# MCU.net
KiCad netlist of a schematic drawn in Altium Designer
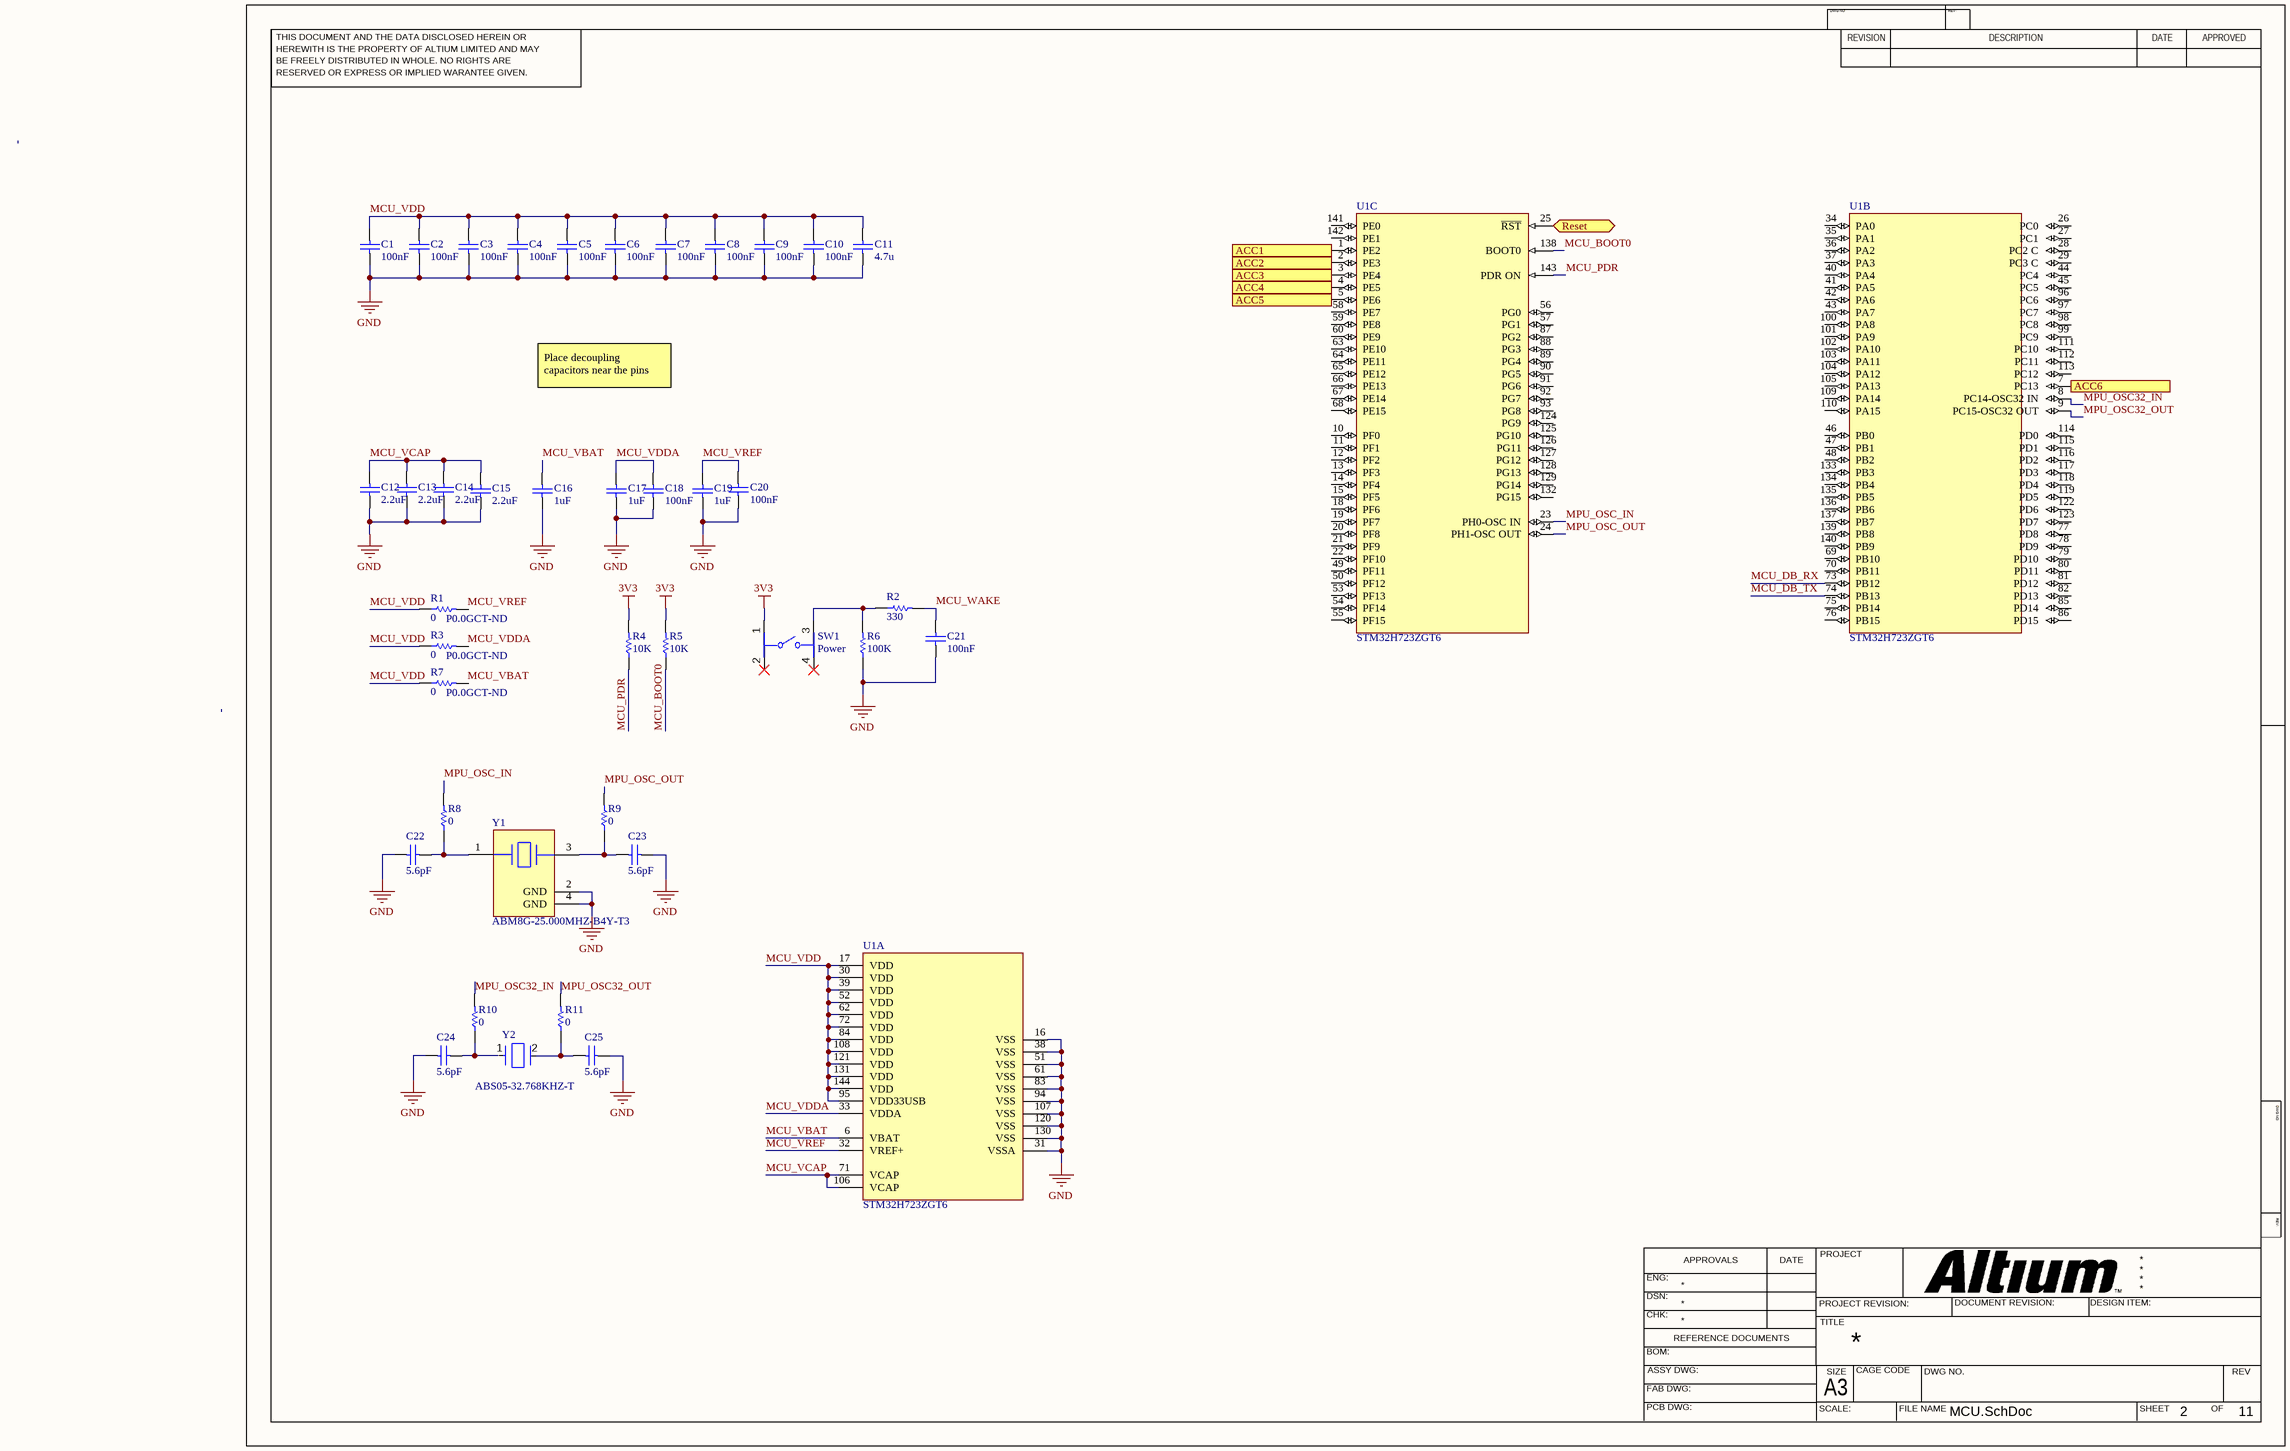
[diagram p0: MCU.SchDoc]

(export (version "E")
  (design (tool "Eeschema 10.0.6"))
  (components
    (comp (ref "C1")
      (value "100nF")
      (description "Capacitor")
      (libsource (lib "Simulation Generic Components") (part "Capacitor"))
    )
    (comp (ref "C2")
      (value "100nF")
      (description "Capacitor")
      (libsource (lib "Simulation Generic Components") (part "Capacitor"))
    )
    (comp (ref "C3")
      (value "100nF")
      (description "Capacitor")
      (libsource (lib "Simulation Generic Components") (part "Capacitor"))
    )
    (comp (ref "C4")
      (value "100nF")
      (description "Capacitor")
      (libsource (lib "Simulation Generic Components") (part "Capacitor"))
    )
    (comp (ref "C5")
      (value "100nF")
      (description "Capacitor")
      (libsource (lib "Simulation Generic Components") (part "Capacitor"))
    )
    (comp (ref "C6")
      (value "100nF")
      (description "Capacitor")
      (libsource (lib "Simulation Generic Components") (part "Capacitor"))
    )
    (comp (ref "C7")
      (value "100nF")
      (description "Capacitor")
      (libsource (lib "Simulation Generic Components") (part "Capacitor"))
    )
    (comp (ref "C8")
      (value "100nF")
      (description "Capacitor")
      (libsource (lib "Simulation Generic Components") (part "Capacitor"))
    )
    (comp (ref "C9")
      (value "100nF")
      (description "Capacitor")
      (libsource (lib "Simulation Generic Components") (part "Capacitor"))
    )
    (comp (ref "C10")
      (value "100nF")
      (description "Capacitor")
      (libsource (lib "Simulation Generic Components") (part "Capacitor"))
    )
    (comp (ref "C11")
      (value "4.7u")
      (description "Capacitor")
      (libsource (lib "Simulation Generic Components") (part "Capacitor"))
    )
    (comp (ref "C12")
      (value "2.2uF")
      (description "Capacitor")
      (libsource (lib "Simulation Generic Components") (part "Capacitor"))
    )
    (comp (ref "C13")
      (value "2.2uF")
      (description "Capacitor")
      (libsource (lib "Simulation Generic Components") (part "Capacitor"))
    )
    (comp (ref "C14")
      (value "2.2uF")
      (description "Capacitor")
      (libsource (lib "Simulation Generic Components") (part "Capacitor"))
    )
    (comp (ref "C15")
      (value "2.2uF")
      (description "Capacitor")
      (libsource (lib "Simulation Generic Components") (part "Capacitor"))
    )
    (comp (ref "C16")
      (value "1uF")
      (description "Capacitor")
      (libsource (lib "Simulation Generic Components") (part "Capacitor"))
    )
    (comp (ref "C17")
      (value "1uF")
      (description "Capacitor")
      (libsource (lib "Simulation Generic Components") (part "Capacitor"))
    )
    (comp (ref "C18")
      (value "100nF")
      (description "Capacitor")
      (libsource (lib "Simulation Generic Components") (part "Capacitor"))
    )
    (comp (ref "C19")
      (value "1uF")
      (description "Capacitor")
      (libsource (lib "Simulation Generic Components") (part "Capacitor"))
    )
    (comp (ref "C20")
      (value "100nF")
      (description "Capacitor")
      (libsource (lib "Simulation Generic Components") (part "Capacitor"))
    )
    (comp (ref "C21")
      (value "100nF")
      (description "Capacitor")
      (libsource (lib "Simulation Generic Components") (part "Capacitor"))
    )
    (comp (ref "C22")
      (value "5.6pF")
      (description "Capacitor")
      (libsource (lib "Simulation Generic Components") (part "Capacitor"))
    )
    (comp (ref "C23")
      (value "5.6pF")
      (description "Capacitor")
      (libsource (lib "Simulation Generic Components") (part "Capacitor"))
    )
    (comp (ref "C24")
      (value "5.6pF")
      (description "Capacitor")
      (libsource (lib "Simulation Generic Components") (part "Capacitor"))
    )
    (comp (ref "C25")
      (value "5.6pF")
      (description "Capacitor")
      (libsource (lib "Simulation Generic Components") (part "Capacitor"))
    )
    (comp (ref "R1")
      (value "0")
      (description "Resistor")
      (fields (field (name "SUPPLIER PART NUMBER 1") "P0.0GCT-ND"))
      (libsource (lib "Simulation Generic Components") (part "Resistor"))
    )
    (comp (ref "R2")
      (value "330")
      (description "Resistor")
      (libsource (lib "Simulation Generic Components") (part "Resistor"))
    )
    (comp (ref "R3")
      (value "0")
      (description "Resistor")
      (fields (field (name "SUPPLIER PART NUMBER 1") "P0.0GCT-ND"))
      (libsource (lib "Simulation Generic Components") (part "Resistor"))
    )
    (comp (ref "R4")
      (value "10K")
      (description "Resistor")
      (libsource (lib "Simulation Generic Components") (part "Resistor"))
    )
    (comp (ref "R5")
      (value "10K")
      (description "Resistor")
      (libsource (lib "Simulation Generic Components") (part "Resistor"))
    )
    (comp (ref "R6")
      (value "100K")
      (description "Resistor")
      (libsource (lib "Simulation Generic Components") (part "Resistor"))
    )
    (comp (ref "R7")
      (value "0")
      (description "Resistor")
      (fields (field (name "SUPPLIER PART NUMBER 1") "P0.0GCT-ND"))
      (libsource (lib "Simulation Generic Components") (part "Resistor"))
    )
    (comp (ref "R8")
      (value "0")
      (description "Resistor")
      (libsource (lib "Simulation Generic Components") (part "Resistor"))
    )
    (comp (ref "R9")
      (value "0")
      (description "Resistor")
      (libsource (lib "Simulation Generic Components") (part "Resistor"))
    )
    (comp (ref "R10")
      (value "0")
      (description "Resistor")
      (libsource (lib "Simulation Generic Components") (part "Resistor"))
    )
    (comp (ref "R11")
      (value "0")
      (description "Resistor")
      (libsource (lib "Simulation Generic Components") (part "Resistor"))
    )
    (comp (ref "SW1")
      (value "Power")
      (footprint "FP-PTS526SK15SMTR2LFS-MFG")
      (description "TACT 5.2 X 5.2, 1.5 MM H, 260GF,")
      (fields
        (field (name "MANUFACTURER") "C&K")
        (field (name "MANUFACTURER PART NUMBER") "PTS526SK15SMTR2LFS")
      )
      (libsource (lib "Altium Content Vault") (part "b8895f3f4cefb76e1819d2863dba89b"))
    )
    (comp (ref "U1")
      (value "STM32H723ZGT6")
      (footprint "FP-LQFP144-1A-IPC_A")
      (description "IC MCU 32BIT 1MB FLASH 144LQFP")
      (libsource (lib "Altium Content Vault") (part "099c9e622ff36f7eb897f9cba6d1f51"))
    )
    (comp (ref "Y1")
      (value "ABM8G-25.000MHZ-B4Y-T3")
      (footprint "FP-ABM8G-MFG")
      (description "Crystal 25MHz ±30ppm (Tol) ±30ppm (Stability) 10pF FUND 60Ω 4-Pin SMD T/R")
      (fields (field (name "TOLERANCE") "30ppm"))
      (libsource (lib "Altium Content Vault") (part "48e526d86b7f2615d98721063c72f49"))
    )
    (comp (ref "Y2")
      (value "ABS05-32.768KHZ-T")
      (footprint "FP-ABS05-MFG")
      (description "Crystal 32.768kHz ±20ppm (Tol) 12.5pF FUND 90kΩ 2-Pin SMD T/R")
      (fields (field (name "TOLERANCE") "20ppm"))
      (libsource (lib "Altium Content Vault") (part "c23a69dc6c9e2f18f2079038eb95dd1"))
    )
  )
  (nets
    (net (code "1") (name "/ACC1") (class "Default")
      (node (ref "U1") (pin "1") (pinfunction "PE2_1") (pintype "bidirectional"))
    )
    (net (code "2") (name "/ACC2") (class "Default")
      (node (ref "U1") (pin "2") (pinfunction "PE3_2") (pintype "bidirectional"))
    )
    (net (code "3") (name "/ACC3") (class "Default")
      (node (ref "U1") (pin "3") (pinfunction "PE4_3") (pintype "bidirectional"))
    )
    (net (code "4") (name "/ACC4") (class "Default")
      (node (ref "U1") (pin "4") (pinfunction "PE5_4") (pintype "bidirectional"))
    )
    (net (code "5") (name "/ACC5") (class "Default")
      (node (ref "U1") (pin "5") (pinfunction "PE6_5") (pintype "bidirectional"))
    )
    (net (code "6") (name "/ACC6") (class "Default")
      (node (ref "U1") (pin "7") (pinfunction "PC13_7") (pintype "bidirectional"))
    )
    (net (code "7") (name "/MCU_BOOT0") (class "Default")
      (node (ref "R5") (pin "1") (pinfunction "1_1") (pintype "passive"))
      (node (ref "U1") (pin "138") (pinfunction "BOOT0_138") (pintype "input"))
    )
    (net (code "8") (name "/MCU_DB_RX") (class "Default")
      (node (ref "U1") (pin "73") (pinfunction "PB12_73") (pintype "bidirectional"))
    )
    (net (code "9") (name "/MCU_DB_TX") (class "Default")
      (node (ref "U1") (pin "74") (pinfunction "PB13_74") (pintype "bidirectional"))
    )
    (net (code "10") (name "/MCU_PDR") (class "Default")
      (node (ref "R4") (pin "1") (pinfunction "1_1") (pintype "passive"))
      (node (ref "U1") (pin "143") (pinfunction "PDR_ON_143") (pintype "input"))
    )
    (net (code "11") (name "/MCU_VBAT") (class "Default")
      (node (ref "C16") (pin "2") (pinfunction "2_2") (pintype "passive"))
      (node (ref "U1") (pin "6") (pinfunction "VBAT_6") (pintype "power_in"))
    )
    (net (code "12") (name "/MCU_VCAP") (class "Default")
      (node (ref "C12") (pin "2") (pinfunction "2_2") (pintype "passive"))
      (node (ref "C13") (pin "2") (pinfunction "2_2") (pintype "passive"))
      (node (ref "C14") (pin "2") (pinfunction "2_2") (pintype "passive"))
      (node (ref "C15") (pin "2") (pinfunction "2_2") (pintype "passive"))
      (node (ref "U1") (pin "106") (pinfunction "VCAP_106") (pintype "power_in"))
      (node (ref "U1") (pin "71") (pinfunction "VCAP_71") (pintype "power_in"))
    )
    (net (code "13") (name "/MCU_VDD") (class "Default")
      (node (ref "C1") (pin "2") (pinfunction "2_2") (pintype "passive"))
      (node (ref "C10") (pin "2") (pinfunction "2_2") (pintype "passive"))
      (node (ref "C11") (pin "2") (pinfunction "2_2") (pintype "passive"))
      (node (ref "C2") (pin "2") (pinfunction "2_2") (pintype "passive"))
      (node (ref "C3") (pin "2") (pinfunction "2_2") (pintype "passive"))
      (node (ref "C4") (pin "2") (pinfunction "2_2") (pintype "passive"))
      (node (ref "C5") (pin "2") (pinfunction "2_2") (pintype "passive"))
      (node (ref "C6") (pin "2") (pinfunction "2_2") (pintype "passive"))
      (node (ref "C7") (pin "2") (pinfunction "2_2") (pintype "passive"))
      (node (ref "C8") (pin "2") (pinfunction "2_2") (pintype "passive"))
      (node (ref "C9") (pin "2") (pinfunction "2_2") (pintype "passive"))
      (node (ref "R1") (pin "1") (pinfunction "1_1") (pintype "passive"))
      (node (ref "R3") (pin "1") (pinfunction "1_1") (pintype "passive"))
      (node (ref "R7") (pin "1") (pinfunction "1_1") (pintype "passive"))
      (node (ref "U1") (pin "108") (pinfunction "VDD_108") (pintype "power_in"))
      (node (ref "U1") (pin "121") (pinfunction "VDD_121") (pintype "power_in"))
      (node (ref "U1") (pin "131") (pinfunction "VDD_131") (pintype "power_in"))
      (node (ref "U1") (pin "144") (pinfunction "VDD_144") (pintype "power_in"))
      (node (ref "U1") (pin "17") (pinfunction "VDD_17") (pintype "power_in"))
      (node (ref "U1") (pin "30") (pinfunction "VDD_30") (pintype "power_in"))
      (node (ref "U1") (pin "39") (pinfunction "VDD_39") (pintype "power_in"))
      (node (ref "U1") (pin "52") (pinfunction "VDD_52") (pintype "power_in"))
      (node (ref "U1") (pin "62") (pinfunction "VDD_62") (pintype "power_in"))
      (node (ref "U1") (pin "72") (pinfunction "VDD_72") (pintype "power_in"))
      (node (ref "U1") (pin "84") (pinfunction "VDD_84") (pintype "power_in"))
      (node (ref "U1") (pin "95") (pinfunction "VDD33USB_95") (pintype "power_in"))
    )
    (net (code "14") (name "/MCU_VDDA") (class "Default")
      (node (ref "C17") (pin "2") (pinfunction "2_2") (pintype "passive"))
      (node (ref "C18") (pin "2") (pinfunction "2_2") (pintype "passive"))
      (node (ref "U1") (pin "33") (pinfunction "VDDA_33") (pintype "power_in"))
    )
    (net (code "15") (name "/MCU_VREF") (class "Default")
      (node (ref "C19") (pin "2") (pinfunction "2_2") (pintype "passive"))
      (node (ref "C20") (pin "2") (pinfunction "2_2") (pintype "passive"))
      (node (ref "U1") (pin "32") (pinfunction "VREF+_32") (pintype "power_in"))
    )
    (net (code "16") (name "/MCU_WAKE") (class "Default")
      (node (ref "C21") (pin "2") (pinfunction "2_2") (pintype "passive"))
      (node (ref "R2") (pin "2") (pinfunction "2_2") (pintype "passive"))
    )
    (net (code "17") (name "/MPU_OSC32_IN") (class "Default")
      (node (ref "R10") (pin "2") (pinfunction "2_2") (pintype "passive"))
      (node (ref "U1") (pin "8") (pinfunction "PC14-OSC32_IN_8") (pintype "bidirectional"))
    )
    (net (code "18") (name "/MPU_OSC32_OUT") (class "Default")
      (node (ref "R11") (pin "2") (pinfunction "2_2") (pintype "passive"))
      (node (ref "U1") (pin "9") (pinfunction "PC15-OSC32_OUT_9") (pintype "bidirectional"))
    )
    (net (code "19") (name "/MPU_OSC_IN") (class "Default")
      (node (ref "R8") (pin "2") (pinfunction "2_2") (pintype "passive"))
      (node (ref "U1") (pin "23") (pinfunction "PH0-OSC_IN_23") (pintype "bidirectional"))
    )
    (net (code "20") (name "/MPU_OSC_OUT") (class "Default")
      (node (ref "R9") (pin "2") (pinfunction "2_2") (pintype "passive"))
      (node (ref "U1") (pin "24") (pinfunction "PH1-OSC_OUT_24") (pintype "bidirectional"))
    )
    (net (code "21") (name "/Reset") (class "Default")
      (node (ref "U1") (pin "25") (pinfunction "~{RST}_25") (pintype "input"))
    )
    (net (code "22") (name "3V3") (class "Default")
      (node (ref "R4") (pin "2") (pinfunction "2_2") (pintype "passive"))
      (node (ref "R5") (pin "2") (pinfunction "2_2") (pintype "passive"))
      (node (ref "SW1") (pin "1") (pinfunction "1_1") (pintype "passive"))
    )
    (net (code "23") (name "GND") (class "Default")
      (node (ref "C1") (pin "1") (pinfunction "1_1") (pintype "passive"))
      (node (ref "C10") (pin "1") (pinfunction "1_1") (pintype "passive"))
      (node (ref "C11") (pin "1") (pinfunction "1_1") (pintype "passive"))
      (node (ref "C12") (pin "1") (pinfunction "1_1") (pintype "passive"))
      (node (ref "C13") (pin "1") (pinfunction "1_1") (pintype "passive"))
      (node (ref "C14") (pin "1") (pinfunction "1_1") (pintype "passive"))
      (node (ref "C15") (pin "1") (pinfunction "1_1") (pintype "passive"))
      (node (ref "C16") (pin "1") (pinfunction "1_1") (pintype "passive"))
      (node (ref "C17") (pin "1") (pinfunction "1_1") (pintype "passive"))
      (node (ref "C18") (pin "1") (pinfunction "1_1") (pintype "passive"))
      (node (ref "C19") (pin "1") (pinfunction "1_1") (pintype "passive"))
      (node (ref "C2") (pin "1") (pinfunction "1_1") (pintype "passive"))
      (node (ref "C20") (pin "1") (pinfunction "1_1") (pintype "passive"))
      (node (ref "C21") (pin "1") (pinfunction "1_1") (pintype "passive"))
      (node (ref "C22") (pin "2") (pinfunction "2_2") (pintype "passive"))
      (node (ref "C23") (pin "1") (pinfunction "1_1") (pintype "passive"))
      (node (ref "C24") (pin "2") (pinfunction "2_2") (pintype "passive"))
      (node (ref "C25") (pin "1") (pinfunction "1_1") (pintype "passive"))
      (node (ref "C3") (pin "1") (pinfunction "1_1") (pintype "passive"))
      (node (ref "C4") (pin "1") (pinfunction "1_1") (pintype "passive"))
      (node (ref "C5") (pin "1") (pinfunction "1_1") (pintype "passive"))
      (node (ref "C6") (pin "1") (pinfunction "1_1") (pintype "passive"))
      (node (ref "C7") (pin "1") (pinfunction "1_1") (pintype "passive"))
      (node (ref "C8") (pin "1") (pinfunction "1_1") (pintype "passive"))
      (node (ref "C9") (pin "1") (pinfunction "1_1") (pintype "passive"))
      (node (ref "R6") (pin "1") (pinfunction "1_1") (pintype "passive"))
      (node (ref "U1") (pin "107") (pinfunction "VSS_107") (pintype "power_in"))
      (node (ref "U1") (pin "120") (pinfunction "VSS_120") (pintype "power_in"))
      (node (ref "U1") (pin "130") (pinfunction "VSS_130") (pintype "power_in"))
      (node (ref "U1") (pin "16") (pinfunction "VSS_16") (pintype "power_in"))
      (node (ref "U1") (pin "31") (pinfunction "VSSA_31") (pintype "power_in"))
      (node (ref "U1") (pin "38") (pinfunction "VSS_38") (pintype "power_in"))
      (node (ref "U1") (pin "51") (pinfunction "VSS_51") (pintype "power_in"))
      (node (ref "U1") (pin "61") (pinfunction "VSS_61") (pintype "power_in"))
      (node (ref "U1") (pin "83") (pinfunction "VSS_83") (pintype "power_in"))
      (node (ref "U1") (pin "94") (pinfunction "VSS_94") (pintype "power_in"))
      (node (ref "Y1") (pin "2") (pinfunction "GND_2") (pintype "power_in"))
      (node (ref "Y1") (pin "4") (pinfunction "GND_4") (pintype "power_in"))
    )
    (net (code "24") (name "Net-(C22-Pad1)") (class "Default")
      (node (ref "C22") (pin "1") (pinfunction "1_1") (pintype "passive"))
      (node (ref "R8") (pin "1") (pinfunction "1_1") (pintype "passive"))
      (node (ref "Y1") (pin "1") (pinfunction "1_1") (pintype "passive"))
    )
    (net (code "25") (name "Net-(C23-Pad2)") (class "Default")
      (node (ref "C23") (pin "2") (pinfunction "2_2") (pintype "passive"))
      (node (ref "R9") (pin "1") (pinfunction "1_1") (pintype "passive"))
      (node (ref "Y1") (pin "3") (pinfunction "3_3") (pintype "passive"))
    )
    (net (code "26") (name "Net-(C24-Pad1)") (class "Default")
      (node (ref "C24") (pin "1") (pinfunction "1_1") (pintype "passive"))
      (node (ref "R10") (pin "1") (pinfunction "1_1") (pintype "passive"))
    )
    (net (code "27") (name "Net-(C25-Pad2)") (class "Default")
      (node (ref "C25") (pin "2") (pinfunction "2_2") (pintype "passive"))
      (node (ref "R11") (pin "1") (pinfunction "1_1") (pintype "passive"))
      (node (ref "Y2") (pin "2") (pinfunction "2_2") (pintype "passive"))
    )
    (net (code "28") (name "Net-(R2-Pad1)") (class "Default")
      (node (ref "R2") (pin "1") (pinfunction "1_1") (pintype "passive"))
      (node (ref "R6") (pin "2") (pinfunction "2_2") (pintype "passive"))
      (node (ref "SW1") (pin "3") (pinfunction "3_3") (pintype "passive"))
    )
    (net (code "29") (name "unconnected-(R1-Pad2)") (class "Default")
      (node (ref "R1") (pin "2") (pinfunction "2_2") (pintype "passive"))
    )
    (net (code "30") (name "unconnected-(R3-Pad2)") (class "Default")
      (node (ref "R3") (pin "2") (pinfunction "2_2") (pintype "passive"))
    )
    (net (code "31") (name "unconnected-(R7-Pad2)") (class "Default")
      (node (ref "R7") (pin "2") (pinfunction "2_2") (pintype "passive"))
    )
    (net (code "32") (name "unconnected-(SW1-Pad2)") (class "Default")
      (node (ref "SW1") (pin "2") (pinfunction "2_2") (pintype "passive+no_connect"))
    )
    (net (code "33") (name "unconnected-(SW1-Pad4)") (class "Default")
      (node (ref "SW1") (pin "4") (pinfunction "4_4") (pintype "passive+no_connect"))
    )
    (net (code "34") (name "unconnected-(U1B-PA0-Pad34)") (class "Default")
      (node (ref "U1") (pin "34") (pinfunction "PA0_34") (pintype "bidirectional"))
    )
    (net (code "35") (name "unconnected-(U1B-PA1-Pad35)") (class "Default")
      (node (ref "U1") (pin "35") (pinfunction "PA1_35") (pintype "bidirectional"))
    )
    (net (code "36") (name "unconnected-(U1B-PA2-Pad36)") (class "Default")
      (node (ref "U1") (pin "36") (pinfunction "PA2_36") (pintype "bidirectional"))
    )
    (net (code "37") (name "unconnected-(U1B-PA3-Pad37)") (class "Default")
      (node (ref "U1") (pin "37") (pinfunction "PA3_37") (pintype "bidirectional"))
    )
    (net (code "38") (name "unconnected-(U1B-PA4-Pad40)") (class "Default")
      (node (ref "U1") (pin "40") (pinfunction "PA4_40") (pintype "bidirectional"))
    )
    (net (code "39") (name "unconnected-(U1B-PA5-Pad41)") (class "Default")
      (node (ref "U1") (pin "41") (pinfunction "PA5_41") (pintype "bidirectional"))
    )
    (net (code "40") (name "unconnected-(U1B-PA6-Pad42)") (class "Default")
      (node (ref "U1") (pin "42") (pinfunction "PA6_42") (pintype "bidirectional"))
    )
    (net (code "41") (name "unconnected-(U1B-PA7-Pad43)") (class "Default")
      (node (ref "U1") (pin "43") (pinfunction "PA7_43") (pintype "bidirectional"))
    )
    (net (code "42") (name "unconnected-(U1B-PA8-Pad100)") (class "Default")
      (node (ref "U1") (pin "100") (pinfunction "PA8_100") (pintype "bidirectional"))
    )
    (net (code "43") (name "unconnected-(U1B-PA9-Pad101)") (class "Default")
      (node (ref "U1") (pin "101") (pinfunction "PA9_101") (pintype "bidirectional"))
    )
    (net (code "44") (name "unconnected-(U1B-PA10-Pad102)") (class "Default")
      (node (ref "U1") (pin "102") (pinfunction "PA10_102") (pintype "bidirectional"))
    )
    (net (code "45") (name "unconnected-(U1B-PA11-Pad103)") (class "Default")
      (node (ref "U1") (pin "103") (pinfunction "PA11_103") (pintype "bidirectional"))
    )
    (net (code "46") (name "unconnected-(U1B-PA12-Pad104)") (class "Default")
      (node (ref "U1") (pin "104") (pinfunction "PA12_104") (pintype "bidirectional"))
    )
    (net (code "47") (name "unconnected-(U1B-PA13-Pad105)") (class "Default")
      (node (ref "U1") (pin "105") (pinfunction "PA13_105") (pintype "bidirectional"))
    )
    (net (code "48") (name "unconnected-(U1B-PA14-Pad109)") (class "Default")
      (node (ref "U1") (pin "109") (pinfunction "PA14_109") (pintype "bidirectional"))
    )
    (net (code "49") (name "unconnected-(U1B-PA15-Pad110)") (class "Default")
      (node (ref "U1") (pin "110") (pinfunction "PA15_110") (pintype "bidirectional"))
    )
    (net (code "50") (name "unconnected-(U1B-PB0-Pad46)") (class "Default")
      (node (ref "U1") (pin "46") (pinfunction "PB0_46") (pintype "bidirectional"))
    )
    (net (code "51") (name "unconnected-(U1B-PB1-Pad47)") (class "Default")
      (node (ref "U1") (pin "47") (pinfunction "PB1_47") (pintype "bidirectional"))
    )
    (net (code "52") (name "unconnected-(U1B-PB2-Pad48)") (class "Default")
      (node (ref "U1") (pin "48") (pinfunction "PB2_48") (pintype "bidirectional"))
    )
    (net (code "53") (name "unconnected-(U1B-PB3-Pad133)") (class "Default")
      (node (ref "U1") (pin "133") (pinfunction "PB3_133") (pintype "bidirectional"))
    )
    (net (code "54") (name "unconnected-(U1B-PB4-Pad134)") (class "Default")
      (node (ref "U1") (pin "134") (pinfunction "PB4_134") (pintype "bidirectional"))
    )
    (net (code "55") (name "unconnected-(U1B-PB5-Pad135)") (class "Default")
      (node (ref "U1") (pin "135") (pinfunction "PB5_135") (pintype "bidirectional"))
    )
    (net (code "56") (name "unconnected-(U1B-PB6-Pad136)") (class "Default")
      (node (ref "U1") (pin "136") (pinfunction "PB6_136") (pintype "bidirectional"))
    )
    (net (code "57") (name "unconnected-(U1B-PB7-Pad137)") (class "Default")
      (node (ref "U1") (pin "137") (pinfunction "PB7_137") (pintype "bidirectional"))
    )
    (net (code "58") (name "unconnected-(U1B-PB8-Pad139)") (class "Default")
      (node (ref "U1") (pin "139") (pinfunction "PB8_139") (pintype "bidirectional"))
    )
    (net (code "59") (name "unconnected-(U1B-PB9-Pad140)") (class "Default")
      (node (ref "U1") (pin "140") (pinfunction "PB9_140") (pintype "bidirectional"))
    )
    (net (code "60") (name "unconnected-(U1B-PB10-Pad69)") (class "Default")
      (node (ref "U1") (pin "69") (pinfunction "PB10_69") (pintype "bidirectional"))
    )
    (net (code "61") (name "unconnected-(U1B-PB11-Pad70)") (class "Default")
      (node (ref "U1") (pin "70") (pinfunction "PB11_70") (pintype "bidirectional"))
    )
    (net (code "62") (name "unconnected-(U1B-PB14-Pad75)") (class "Default")
      (node (ref "U1") (pin "75") (pinfunction "PB14_75") (pintype "bidirectional"))
    )
    (net (code "63") (name "unconnected-(U1B-PB15-Pad76)") (class "Default")
      (node (ref "U1") (pin "76") (pinfunction "PB15_76") (pintype "bidirectional"))
    )
    (net (code "64") (name "unconnected-(U1B-PC0-Pad26)") (class "Default")
      (node (ref "U1") (pin "26") (pinfunction "PC0_26") (pintype "bidirectional"))
    )
    (net (code "65") (name "unconnected-(U1B-PC1-Pad27)") (class "Default")
      (node (ref "U1") (pin "27") (pinfunction "PC1_27") (pintype "bidirectional"))
    )
    (net (code "66") (name "unconnected-(U1B-PC2_C-Pad28)") (class "Default")
      (node (ref "U1") (pin "28") (pinfunction "PC2_C_28") (pintype "bidirectional"))
    )
    (net (code "67") (name "unconnected-(U1B-PC3_C-Pad29)") (class "Default")
      (node (ref "U1") (pin "29") (pinfunction "PC3_C_29") (pintype "bidirectional"))
    )
    (net (code "68") (name "unconnected-(U1B-PC4-Pad44)") (class "Default")
      (node (ref "U1") (pin "44") (pinfunction "PC4_44") (pintype "bidirectional"))
    )
    (net (code "69") (name "unconnected-(U1B-PC5-Pad45)") (class "Default")
      (node (ref "U1") (pin "45") (pinfunction "PC5_45") (pintype "bidirectional"))
    )
    (net (code "70") (name "unconnected-(U1B-PC6-Pad96)") (class "Default")
      (node (ref "U1") (pin "96") (pinfunction "PC6_96") (pintype "bidirectional"))
    )
    (net (code "71") (name "unconnected-(U1B-PC7-Pad97)") (class "Default")
      (node (ref "U1") (pin "97") (pinfunction "PC7_97") (pintype "bidirectional"))
    )
    (net (code "72") (name "unconnected-(U1B-PC8-Pad98)") (class "Default")
      (node (ref "U1") (pin "98") (pinfunction "PC8_98") (pintype "bidirectional"))
    )
    (net (code "73") (name "unconnected-(U1B-PC9-Pad99)") (class "Default")
      (node (ref "U1") (pin "99") (pinfunction "PC9_99") (pintype "bidirectional"))
    )
    (net (code "74") (name "unconnected-(U1B-PC10-Pad111)") (class "Default")
      (node (ref "U1") (pin "111") (pinfunction "PC10_111") (pintype "bidirectional"))
    )
    (net (code "75") (name "unconnected-(U1B-PC11-Pad112)") (class "Default")
      (node (ref "U1") (pin "112") (pinfunction "PC11_112") (pintype "bidirectional"))
    )
    (net (code "76") (name "unconnected-(U1B-PC12-Pad113)") (class "Default")
      (node (ref "U1") (pin "113") (pinfunction "PC12_113") (pintype "bidirectional"))
    )
    (net (code "77") (name "unconnected-(U1B-PD0-Pad114)") (class "Default")
      (node (ref "U1") (pin "114") (pinfunction "PD0_114") (pintype "bidirectional"))
    )
    (net (code "78") (name "unconnected-(U1B-PD1-Pad115)") (class "Default")
      (node (ref "U1") (pin "115") (pinfunction "PD1_115") (pintype "bidirectional"))
    )
    (net (code "79") (name "unconnected-(U1B-PD2-Pad116)") (class "Default")
      (node (ref "U1") (pin "116") (pinfunction "PD2_116") (pintype "bidirectional"))
    )
    (net (code "80") (name "unconnected-(U1B-PD3-Pad117)") (class "Default")
      (node (ref "U1") (pin "117") (pinfunction "PD3_117") (pintype "bidirectional"))
    )
    (net (code "81") (name "unconnected-(U1B-PD4-Pad118)") (class "Default")
      (node (ref "U1") (pin "118") (pinfunction "PD4_118") (pintype "bidirectional"))
    )
    (net (code "82") (name "unconnected-(U1B-PD5-Pad119)") (class "Default")
      (node (ref "U1") (pin "119") (pinfunction "PD5_119") (pintype "bidirectional"))
    )
    (net (code "83") (name "unconnected-(U1B-PD6-Pad122)") (class "Default")
      (node (ref "U1") (pin "122") (pinfunction "PD6_122") (pintype "bidirectional"))
    )
    (net (code "84") (name "unconnected-(U1B-PD7-Pad123)") (class "Default")
      (node (ref "U1") (pin "123") (pinfunction "PD7_123") (pintype "bidirectional"))
    )
    (net (code "85") (name "unconnected-(U1B-PD8-Pad77)") (class "Default")
      (node (ref "U1") (pin "77") (pinfunction "PD8_77") (pintype "bidirectional"))
    )
    (net (code "86") (name "unconnected-(U1B-PD9-Pad78)") (class "Default")
      (node (ref "U1") (pin "78") (pinfunction "PD9_78") (pintype "bidirectional"))
    )
    (net (code "87") (name "unconnected-(U1B-PD10-Pad79)") (class "Default")
      (node (ref "U1") (pin "79") (pinfunction "PD10_79") (pintype "bidirectional"))
    )
    (net (code "88") (name "unconnected-(U1B-PD11-Pad80)") (class "Default")
      (node (ref "U1") (pin "80") (pinfunction "PD11_80") (pintype "bidirectional"))
    )
    (net (code "89") (name "unconnected-(U1B-PD12-Pad81)") (class "Default")
      (node (ref "U1") (pin "81") (pinfunction "PD12_81") (pintype "bidirectional"))
    )
    (net (code "90") (name "unconnected-(U1B-PD13-Pad82)") (class "Default")
      (node (ref "U1") (pin "82") (pinfunction "PD13_82") (pintype "bidirectional"))
    )
    (net (code "91") (name "unconnected-(U1B-PD14-Pad85)") (class "Default")
      (node (ref "U1") (pin "85") (pinfunction "PD14_85") (pintype "bidirectional"))
    )
    (net (code "92") (name "unconnected-(U1B-PD15-Pad86)") (class "Default")
      (node (ref "U1") (pin "86") (pinfunction "PD15_86") (pintype "bidirectional"))
    )
    (net (code "93") (name "unconnected-(U1C-PE0-Pad141)") (class "Default")
      (node (ref "U1") (pin "141") (pinfunction "PE0_141") (pintype "bidirectional"))
    )
    (net (code "94") (name "unconnected-(U1C-PE1-Pad142)") (class "Default")
      (node (ref "U1") (pin "142") (pinfunction "PE1_142") (pintype "bidirectional"))
    )
    (net (code "95") (name "unconnected-(U1C-PE7-Pad58)") (class "Default")
      (node (ref "U1") (pin "58") (pinfunction "PE7_58") (pintype "bidirectional"))
    )
    (net (code "96") (name "unconnected-(U1C-PE8-Pad59)") (class "Default")
      (node (ref "U1") (pin "59") (pinfunction "PE8_59") (pintype "bidirectional"))
    )
    (net (code "97") (name "unconnected-(U1C-PE9-Pad60)") (class "Default")
      (node (ref "U1") (pin "60") (pinfunction "PE9_60") (pintype "bidirectional"))
    )
    (net (code "98") (name "unconnected-(U1C-PE10-Pad63)") (class "Default")
      (node (ref "U1") (pin "63") (pinfunction "PE10_63") (pintype "bidirectional"))
    )
    (net (code "99") (name "unconnected-(U1C-PE11-Pad64)") (class "Default")
      (node (ref "U1") (pin "64") (pinfunction "PE11_64") (pintype "bidirectional"))
    )
    (net (code "100") (name "unconnected-(U1C-PE12-Pad65)") (class "Default")
      (node (ref "U1") (pin "65") (pinfunction "PE12_65") (pintype "bidirectional"))
    )
    (net (code "101") (name "unconnected-(U1C-PE13-Pad66)") (class "Default")
      (node (ref "U1") (pin "66") (pinfunction "PE13_66") (pintype "bidirectional"))
    )
    (net (code "102") (name "unconnected-(U1C-PE14-Pad67)") (class "Default")
      (node (ref "U1") (pin "67") (pinfunction "PE14_67") (pintype "bidirectional"))
    )
    (net (code "103") (name "unconnected-(U1C-PE15-Pad68)") (class "Default")
      (node (ref "U1") (pin "68") (pinfunction "PE15_68") (pintype "bidirectional"))
    )
    (net (code "104") (name "unconnected-(U1C-PF0-Pad10)") (class "Default")
      (node (ref "U1") (pin "10") (pinfunction "PF0_10") (pintype "bidirectional"))
    )
    (net (code "105") (name "unconnected-(U1C-PF1-Pad11)") (class "Default")
      (node (ref "U1") (pin "11") (pinfunction "PF1_11") (pintype "bidirectional"))
    )
    (net (code "106") (name "unconnected-(U1C-PF2-Pad12)") (class "Default")
      (node (ref "U1") (pin "12") (pinfunction "PF2_12") (pintype "bidirectional"))
    )
    (net (code "107") (name "unconnected-(U1C-PF3-Pad13)") (class "Default")
      (node (ref "U1") (pin "13") (pinfunction "PF3_13") (pintype "bidirectional"))
    )
    (net (code "108") (name "unconnected-(U1C-PF4-Pad14)") (class "Default")
      (node (ref "U1") (pin "14") (pinfunction "PF4_14") (pintype "bidirectional"))
    )
    (net (code "109") (name "unconnected-(U1C-PF5-Pad15)") (class "Default")
      (node (ref "U1") (pin "15") (pinfunction "PF5_15") (pintype "bidirectional"))
    )
    (net (code "110") (name "unconnected-(U1C-PF6-Pad18)") (class "Default")
      (node (ref "U1") (pin "18") (pinfunction "PF6_18") (pintype "bidirectional"))
    )
    (net (code "111") (name "unconnected-(U1C-PF7-Pad19)") (class "Default")
      (node (ref "U1") (pin "19") (pinfunction "PF7_19") (pintype "bidirectional"))
    )
    (net (code "112") (name "unconnected-(U1C-PF8-Pad20)") (class "Default")
      (node (ref "U1") (pin "20") (pinfunction "PF8_20") (pintype "bidirectional"))
    )
    (net (code "113") (name "unconnected-(U1C-PF9-Pad21)") (class "Default")
      (node (ref "U1") (pin "21") (pinfunction "PF9_21") (pintype "bidirectional"))
    )
    (net (code "114") (name "unconnected-(U1C-PF10-Pad22)") (class "Default")
      (node (ref "U1") (pin "22") (pinfunction "PF10_22") (pintype "bidirectional"))
    )
    (net (code "115") (name "unconnected-(U1C-PF11-Pad49)") (class "Default")
      (node (ref "U1") (pin "49") (pinfunction "PF11_49") (pintype "bidirectional"))
    )
    (net (code "116") (name "unconnected-(U1C-PF12-Pad50)") (class "Default")
      (node (ref "U1") (pin "50") (pinfunction "PF12_50") (pintype "bidirectional"))
    )
    (net (code "117") (name "unconnected-(U1C-PF13-Pad53)") (class "Default")
      (node (ref "U1") (pin "53") (pinfunction "PF13_53") (pintype "bidirectional"))
    )
    (net (code "118") (name "unconnected-(U1C-PF14-Pad54)") (class "Default")
      (node (ref "U1") (pin "54") (pinfunction "PF14_54") (pintype "bidirectional"))
    )
    (net (code "119") (name "unconnected-(U1C-PF15-Pad55)") (class "Default")
      (node (ref "U1") (pin "55") (pinfunction "PF15_55") (pintype "bidirectional"))
    )
    (net (code "120") (name "unconnected-(U1C-PG0-Pad56)") (class "Default")
      (node (ref "U1") (pin "56") (pinfunction "PG0_56") (pintype "bidirectional"))
    )
    (net (code "121") (name "unconnected-(U1C-PG1-Pad57)") (class "Default")
      (node (ref "U1") (pin "57") (pinfunction "PG1_57") (pintype "bidirectional"))
    )
    (net (code "122") (name "unconnected-(U1C-PG2-Pad87)") (class "Default")
      (node (ref "U1") (pin "87") (pinfunction "PG2_87") (pintype "bidirectional"))
    )
    (net (code "123") (name "unconnected-(U1C-PG3-Pad88)") (class "Default")
      (node (ref "U1") (pin "88") (pinfunction "PG3_88") (pintype "bidirectional"))
    )
    (net (code "124") (name "unconnected-(U1C-PG4-Pad89)") (class "Default")
      (node (ref "U1") (pin "89") (pinfunction "PG4_89") (pintype "bidirectional"))
    )
    (net (code "125") (name "unconnected-(U1C-PG5-Pad90)") (class "Default")
      (node (ref "U1") (pin "90") (pinfunction "PG5_90") (pintype "bidirectional"))
    )
    (net (code "126") (name "unconnected-(U1C-PG6-Pad91)") (class "Default")
      (node (ref "U1") (pin "91") (pinfunction "PG6_91") (pintype "bidirectional"))
    )
    (net (code "127") (name "unconnected-(U1C-PG7-Pad92)") (class "Default")
      (node (ref "U1") (pin "92") (pinfunction "PG7_92") (pintype "bidirectional"))
    )
    (net (code "128") (name "unconnected-(U1C-PG8-Pad93)") (class "Default")
      (node (ref "U1") (pin "93") (pinfunction "PG8_93") (pintype "bidirectional"))
    )
    (net (code "129") (name "unconnected-(U1C-PG9-Pad124)") (class "Default")
      (node (ref "U1") (pin "124") (pinfunction "PG9_124") (pintype "bidirectional"))
    )
    (net (code "130") (name "unconnected-(U1C-PG10-Pad125)") (class "Default")
      (node (ref "U1") (pin "125") (pinfunction "PG10_125") (pintype "bidirectional"))
    )
    (net (code "131") (name "unconnected-(U1C-PG11-Pad126)") (class "Default")
      (node (ref "U1") (pin "126") (pinfunction "PG11_126") (pintype "bidirectional"))
    )
    (net (code "132") (name "unconnected-(U1C-PG12-Pad127)") (class "Default")
      (node (ref "U1") (pin "127") (pinfunction "PG12_127") (pintype "bidirectional"))
    )
    (net (code "133") (name "unconnected-(U1C-PG13-Pad128)") (class "Default")
      (node (ref "U1") (pin "128") (pinfunction "PG13_128") (pintype "bidirectional"))
    )
    (net (code "134") (name "unconnected-(U1C-PG14-Pad129)") (class "Default")
      (node (ref "U1") (pin "129") (pinfunction "PG14_129") (pintype "bidirectional"))
    )
    (net (code "135") (name "unconnected-(U1C-PG15-Pad132)") (class "Default")
      (node (ref "U1") (pin "132") (pinfunction "PG15_132") (pintype "bidirectional"))
    )
    (net (code "136") (name "unconnected-(Y2-Pad1)") (class "Default")
      (node (ref "Y2") (pin "1") (pinfunction "1_1") (pintype "passive"))
    )
  )
)
